# mdv2.net
KiCad netlist of a schematic drawn in EAGLE
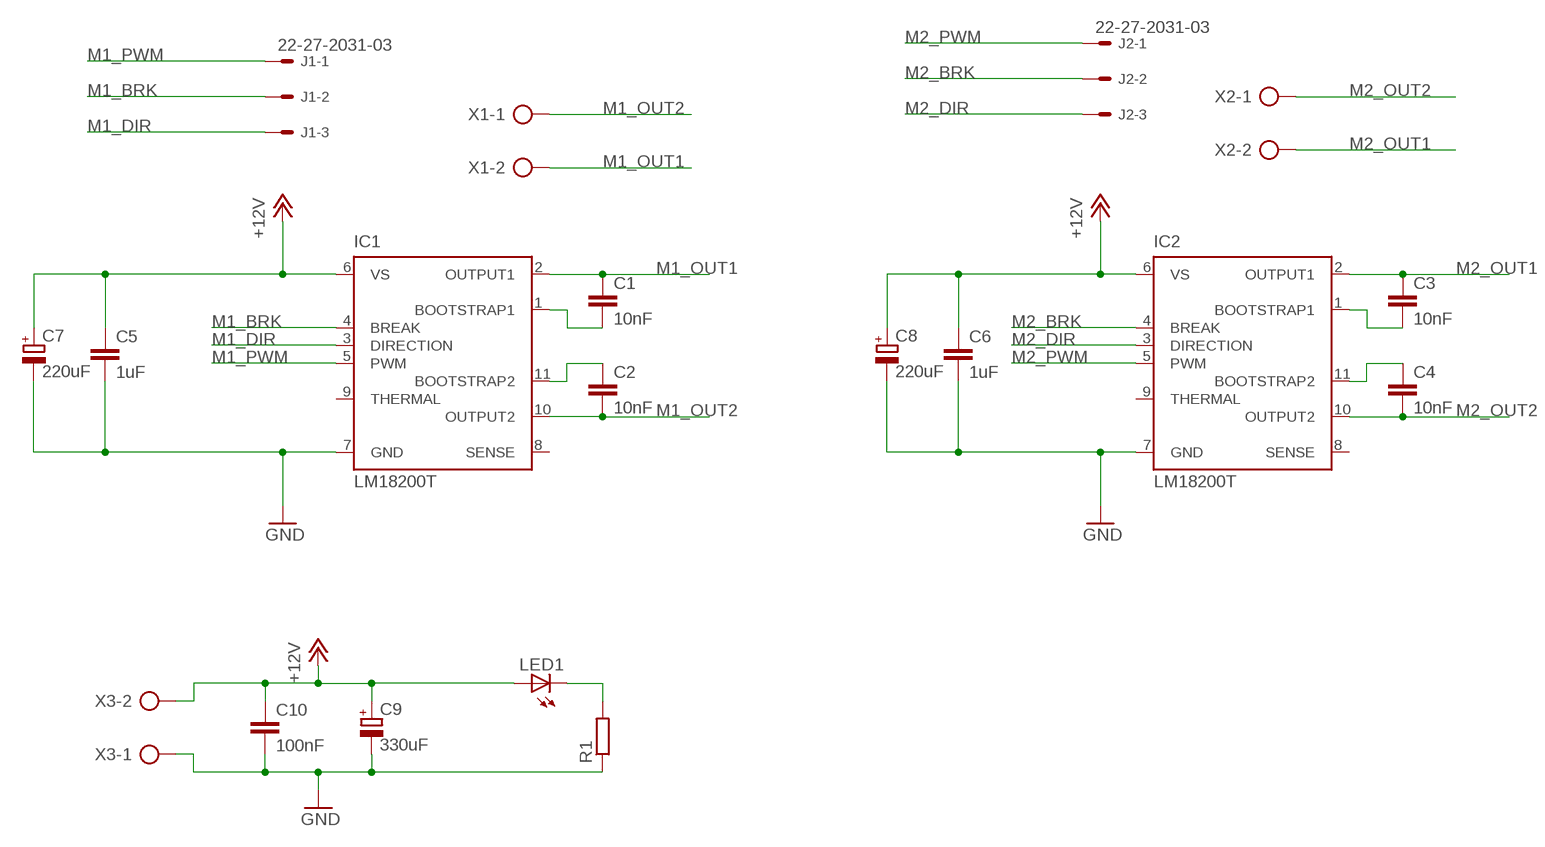
[diagram p0: schematic, sheet 1]

(export (version "E")
  (design (tool "Eeschema 10.0.6"))
  (components
    (comp (ref "C1")
      (value "10nF")
      (footprint "eagle-import:C050-025X075")
      (libsource (lib "eagle-import") (part "C-EU050-025X075"))
    )
    (comp (ref "C2")
      (value "10nF")
      (footprint "eagle-import:C050-025X075")
      (libsource (lib "eagle-import") (part "C-EU050-025X075"))
    )
    (comp (ref "C3")
      (value "10nF")
      (footprint "eagle-import:C050-025X075")
      (libsource (lib "eagle-import") (part "C-EU050-025X075"))
    )
    (comp (ref "C4")
      (value "10nF")
      (footprint "eagle-import:C050-025X075")
      (libsource (lib "eagle-import") (part "C-EU050-025X075"))
    )
    (comp (ref "C5")
      (value "1uF")
      (footprint "eagle-import:C050-045X075")
      (libsource (lib "eagle-import") (part "C-EU050-045X075"))
    )
    (comp (ref "C6")
      (value "1uF")
      (footprint "eagle-import:C050-045X075")
      (libsource (lib "eagle-import") (part "C-EU050-045X075"))
    )
    (comp (ref "C7")
      (value "220uF")
      (footprint "eagle-import:E3,5-8")
      (libsource (lib "eagle-import") (part "CPOL-EUE3.5-8"))
    )
    (comp (ref "C8")
      (value "220uF")
      (footprint "eagle-import:E3,5-8")
      (libsource (lib "eagle-import") (part "CPOL-EUE3.5-8"))
    )
    (comp (ref "C9")
      (value "330uF")
      (footprint "eagle-import:E3,5-8")
      (libsource (lib "eagle-import") (part "CPOL-EUE3.5-8"))
    )
    (comp (ref "C10")
      (value "100nF")
      (footprint "eagle-import:C050-025X075")
      (libsource (lib "eagle-import") (part "C-EU050-025X075"))
    )
    (comp (ref "IC1")
      (value "LM18200T")
      (footprint "eagle-import:TO-220-11")
      (libsource (lib "eagle-import") (part "LM18200T"))
    )
    (comp (ref "IC2")
      (value "LM18200T")
      (footprint "eagle-import:TO-220-11")
      (libsource (lib "eagle-import") (part "LM18200T"))
    )
    (comp (ref "J1")
      (value "22-27-2031-03")
      (footprint "eagle-import:6410-03")
      (libsource (lib "eagle-import") (part "22-?-0327-2031"))
    )
    (comp (ref "J2")
      (value "22-27-2031-03")
      (footprint "eagle-import:6410-03")
      (libsource (lib "eagle-import") (part "22-?-0327-2031"))
    )
    (comp (ref "LED1")
      (value "LED5MM")
      (footprint "eagle-import:LED5MM")
      (libsource (lib "eagle-import") (part "LED5MM"))
    )
    (comp (ref "R1")
      (value "R-EU_0207/7")
      (footprint "eagle-import:0207_7")
      (libsource (lib "eagle-import") (part "R-EU_0207/7"))
    )
    (comp (ref "X1")
      (value "AK300/2")
      (footprint "eagle-import:AK300_2")
      (libsource (lib "eagle-import") (part "AK300/2"))
    )
    (comp (ref "X2")
      (value "AK300/2")
      (footprint "eagle-import:AK300_2")
      (libsource (lib "eagle-import") (part "AK300/2"))
    )
    (comp (ref "X3")
      (value "AK300/2")
      (footprint "eagle-import:AK300_2")
      (libsource (lib "eagle-import") (part "AK300/2"))
    )
  )
  (nets
    (net (code "1") (name "+12V") (class "Default")
      (node (ref "C10") (pin "1") (pinfunction "1_1") (pintype "passive"))
      (node (ref "C5") (pin "1") (pinfunction "1_1") (pintype "passive"))
      (node (ref "C6") (pin "1") (pinfunction "1_1") (pintype "passive"))
      (node (ref "C7") (pin "+") (pinfunction "+_+") (pintype "passive"))
      (node (ref "C8") (pin "+") (pinfunction "+_+") (pintype "passive"))
      (node (ref "C9") (pin "+") (pinfunction "+_+") (pintype "passive"))
      (node (ref "IC1") (pin "6") (pinfunction "VS_6") (pintype "power_in"))
      (node (ref "IC2") (pin "6") (pinfunction "VS_6") (pintype "power_in"))
      (node (ref "LED1") (pin "A") (pinfunction "A_A") (pintype "passive"))
      (node (ref "X3") (pin "2") (pinfunction "KL_2") (pintype "passive"))
    )
    (net (code "2") (name "/M1_BRK") (class "Default")
      (node (ref "IC1") (pin "4") (pinfunction "BREAK_4") (pintype "input"))
      (node (ref "J1") (pin "2") (pinfunction "S_2") (pintype "passive"))
    )
    (net (code "3") (name "/M1_DIR") (class "Default")
      (node (ref "IC1") (pin "3") (pinfunction "DIRECTION_3") (pintype "input"))
      (node (ref "J1") (pin "3") (pinfunction "S_3") (pintype "passive"))
    )
    (net (code "4") (name "/M1_OUT1") (class "Default")
      (node (ref "C1") (pin "1") (pinfunction "1_1") (pintype "passive"))
      (node (ref "IC1") (pin "2") (pinfunction "OUTPUT1_2") (pintype "output"))
      (node (ref "X1") (pin "2") (pinfunction "KL_2") (pintype "passive"))
    )
    (net (code "5") (name "/M1_OUT2") (class "Default")
      (node (ref "C2") (pin "2") (pinfunction "2_2") (pintype "passive"))
      (node (ref "IC1") (pin "10") (pinfunction "OUTPUT2_10") (pintype "output"))
      (node (ref "X1") (pin "1") (pinfunction "KL_1") (pintype "passive"))
    )
    (net (code "6") (name "/M1_PWM") (class "Default")
      (node (ref "IC1") (pin "5") (pinfunction "PWM_5") (pintype "input"))
      (node (ref "J1") (pin "1") (pinfunction "S_1") (pintype "passive"))
    )
    (net (code "7") (name "/M2_BRK") (class "Default")
      (node (ref "IC2") (pin "4") (pinfunction "BREAK_4") (pintype "input"))
      (node (ref "J2") (pin "2") (pinfunction "S_2") (pintype "passive"))
    )
    (net (code "8") (name "/M2_DIR") (class "Default")
      (node (ref "IC2") (pin "3") (pinfunction "DIRECTION_3") (pintype "input"))
      (node (ref "J2") (pin "3") (pinfunction "S_3") (pintype "passive"))
    )
    (net (code "9") (name "/M2_OUT1") (class "Default")
      (node (ref "C3") (pin "1") (pinfunction "1_1") (pintype "passive"))
      (node (ref "IC2") (pin "2") (pinfunction "OUTPUT1_2") (pintype "output"))
      (node (ref "X2") (pin "2") (pinfunction "KL_2") (pintype "passive"))
    )
    (net (code "10") (name "/M2_OUT2") (class "Default")
      (node (ref "C4") (pin "2") (pinfunction "2_2") (pintype "passive"))
      (node (ref "IC2") (pin "10") (pinfunction "OUTPUT2_10") (pintype "output"))
      (node (ref "X2") (pin "1") (pinfunction "KL_1") (pintype "passive"))
    )
    (net (code "11") (name "/M2_PWM") (class "Default")
      (node (ref "IC2") (pin "5") (pinfunction "PWM_5") (pintype "input"))
      (node (ref "J2") (pin "1") (pinfunction "S_1") (pintype "passive"))
    )
    (net (code "12") (name "GND") (class "Default")
      (node (ref "C10") (pin "2") (pinfunction "2_2") (pintype "passive"))
      (node (ref "C5") (pin "2") (pinfunction "2_2") (pintype "passive"))
      (node (ref "C6") (pin "2") (pinfunction "2_2") (pintype "passive"))
      (node (ref "C7") (pin "-") (pinfunction "-_-") (pintype "passive"))
      (node (ref "C8") (pin "-") (pinfunction "-_-") (pintype "passive"))
      (node (ref "C9") (pin "-") (pinfunction "-_-") (pintype "passive"))
      (node (ref "IC1") (pin "7") (pinfunction "GND_7") (pintype "power_in"))
      (node (ref "IC2") (pin "7") (pinfunction "GND_7") (pintype "power_in"))
      (node (ref "R1") (pin "1") (pinfunction "1_1") (pintype "passive"))
      (node (ref "X3") (pin "1") (pinfunction "KL_1") (pintype "passive"))
    )
    (net (code "13") (name "Net-(IC1-BOOTSTRAP1)") (class "Default")
      (node (ref "C1") (pin "2") (pinfunction "2_2") (pintype "passive"))
      (node (ref "IC1") (pin "1") (pinfunction "BOOTSTRAP1_1") (pintype "input"))
    )
    (net (code "14") (name "Net-(IC1-BOOTSTRAP2)") (class "Default")
      (node (ref "C2") (pin "1") (pinfunction "1_1") (pintype "passive"))
      (node (ref "IC1") (pin "11") (pinfunction "BOOTSTRAP2_11") (pintype "input"))
    )
    (net (code "15") (name "Net-(IC2-BOOTSTRAP1)") (class "Default")
      (node (ref "C3") (pin "2") (pinfunction "2_2") (pintype "passive"))
      (node (ref "IC2") (pin "1") (pinfunction "BOOTSTRAP1_1") (pintype "input"))
    )
    (net (code "16") (name "Net-(IC2-BOOTSTRAP2)") (class "Default")
      (node (ref "C4") (pin "1") (pinfunction "1_1") (pintype "passive"))
      (node (ref "IC2") (pin "11") (pinfunction "BOOTSTRAP2_11") (pintype "input"))
    )
    (net (code "17") (name "Net-(LED1-C)") (class "Default")
      (node (ref "LED1") (pin "K") (pinfunction "C_K") (pintype "passive"))
      (node (ref "R1") (pin "2") (pinfunction "2_2") (pintype "passive"))
    )
    (net (code "18") (name "unconnected-(IC1-SENSE-Pad8)") (class "Default")
      (node (ref "IC1") (pin "8") (pinfunction "SENSE_8") (pintype "output"))
    )
    (net (code "19") (name "unconnected-(IC1-THERMAL-Pad9)") (class "Default")
      (node (ref "IC1") (pin "9") (pinfunction "THERMAL_9") (pintype "output"))
    )
    (net (code "20") (name "unconnected-(IC2-SENSE-Pad8)") (class "Default")
      (node (ref "IC2") (pin "8") (pinfunction "SENSE_8") (pintype "output"))
    )
    (net (code "21") (name "unconnected-(IC2-THERMAL-Pad9)") (class "Default")
      (node (ref "IC2") (pin "9") (pinfunction "THERMAL_9") (pintype "output"))
    )
  )
)
